# connectors.net
KiCad netlist of a schematic drawn in Altium Designer
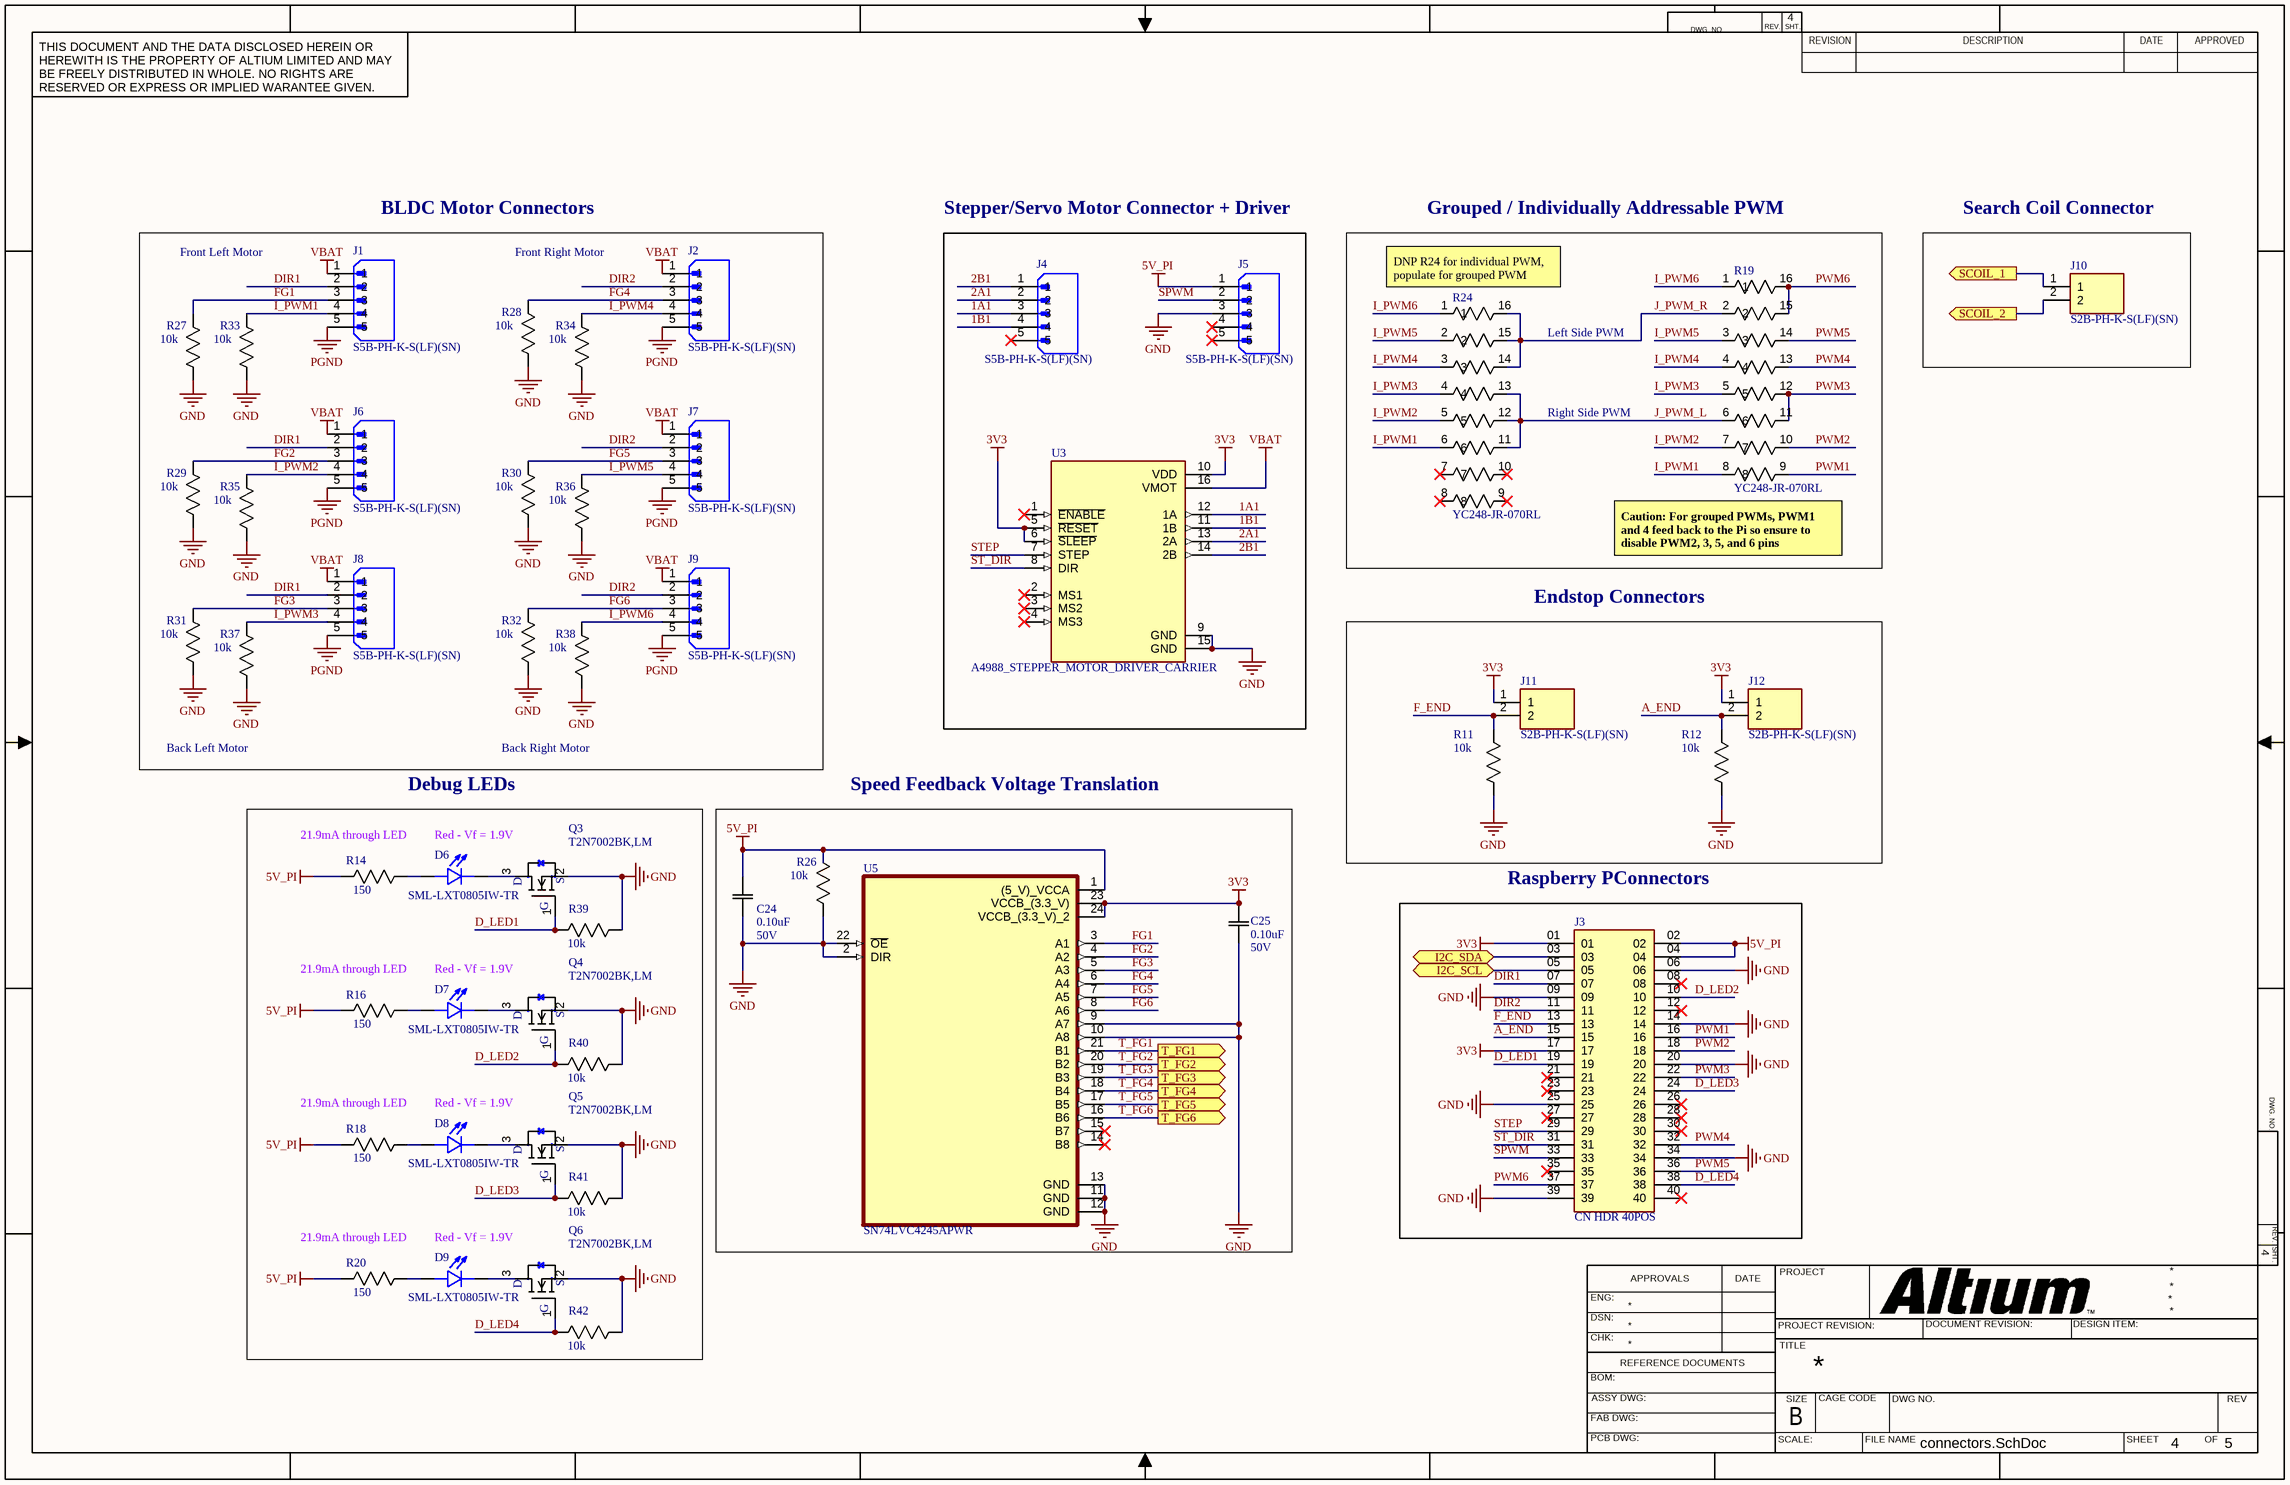
[diagram p0: connectors.SchDoc]

(export (version "E")
  (design (tool "Eeschema 10.0.6"))
  (components
    (comp (ref "C24")
      (value "0.10uF")
      (footprint "0805")
      (description "Default Symbol for Capacitors")
      (fields
        (field (name "RATING") "50V")
        (field (name "PART NUMBER") "CAP 0.1uF 50V")
        (field (name "TOLERANCE") "10%")
      )
      (libsource (lib "capacitor_library") (part "CAP_Default"))
    )
    (comp (ref "C25")
      (value "0.10uF")
      (footprint "0805")
      (description "Default Symbol for Capacitors")
      (fields
        (field (name "RATING") "50V")
        (field (name "PART NUMBER") "CAP 0.1uF 50V")
        (field (name "TOLERANCE") "10%")
      )
      (libsource (lib "capacitor_library") (part "CAP_Default"))
    )
    (comp (ref "D6")
      (value "SML-LXT0805IW-TR")
      (footprint "LEDC2012X120N")
      (fields (field (name "MF") "Lumex Opto/Components"))
      (libsource (lib "SML-LXT0805IW-TR") (part "SML-LXT0805IW-TR"))
    )
    (comp (ref "D7")
      (value "SML-LXT0805IW-TR")
      (footprint "LEDC2012X120N")
      (fields (field (name "MF") "Lumex Opto/Components"))
      (libsource (lib "SML-LXT0805IW-TR") (part "SML-LXT0805IW-TR"))
    )
    (comp (ref "D8")
      (value "SML-LXT0805IW-TR")
      (footprint "LEDC2012X120N")
      (fields (field (name "MF") "Lumex Opto/Components"))
      (libsource (lib "SML-LXT0805IW-TR") (part "SML-LXT0805IW-TR"))
    )
    (comp (ref "D9")
      (value "SML-LXT0805IW-TR")
      (footprint "LEDC2012X120N")
      (fields (field (name "MF") "Lumex Opto/Components"))
      (libsource (lib "SML-LXT0805IW-TR") (part "SML-LXT0805IW-TR"))
    )
    (comp (ref "J1")
      (value "S5B-PH-K-S(LF)(SN)")
      (footprint "JST_S5B-PH-K-S(LF)(SN)")
      (description "Connector Header Through Hole, Right Angle 5 position 0.079 (2.00mm)")
      (fields (field (name "MF") "JST Sales America Inc."))
      (libsource (lib "S5B-PH-K-S_LF__SN_") (part "S5B-PH-K-S(LF)(SN)"))
    )
    (comp (ref "J2")
      (value "S5B-PH-K-S(LF)(SN)")
      (footprint "JST_S5B-PH-K-S(LF)(SN)")
      (description "Connector Header Through Hole, Right Angle 5 position 0.079 (2.00mm)")
      (fields (field (name "MF") "JST Sales America Inc."))
      (libsource (lib "S5B-PH-K-S_LF__SN_") (part "S5B-PH-K-S(LF)(SN)"))
    )
    (comp (ref "J3")
      (value "CN HDR 40POS")
      (footprint "CN HDR 40POS 0.1 TH")
      (description "40 Position Header Connector")
      (libsource (lib "Connector_Library") (part "CN HDR 40POS"))
    )
    (comp (ref "J4")
      (value "S5B-PH-K-S(LF)(SN)")
      (footprint "JST_S5B-PH-K-S(LF)(SN)")
      (description "Connector Header Through Hole, Right Angle 5 position 0.079 (2.00mm)")
      (fields (field (name "MF") "JST Sales America Inc."))
      (libsource (lib "S5B-PH-K-S_LF__SN_") (part "S5B-PH-K-S(LF)(SN)"))
    )
    (comp (ref "J5")
      (value "S5B-PH-K-S(LF)(SN)")
      (footprint "JST_S5B-PH-K-S(LF)(SN)")
      (description "Connector Header Through Hole, Right Angle 5 position 0.079 (2.00mm)")
      (fields (field (name "MF") "JST Sales America Inc."))
      (libsource (lib "S5B-PH-K-S_LF__SN_") (part "S5B-PH-K-S(LF)(SN)"))
    )
    (comp (ref "J6")
      (value "S5B-PH-K-S(LF)(SN)")
      (footprint "JST_S5B-PH-K-S(LF)(SN)")
      (description "Connector Header Through Hole, Right Angle 5 position 0.079 (2.00mm)")
      (fields (field (name "MF") "JST Sales America Inc."))
      (libsource (lib "S5B-PH-K-S_LF__SN_") (part "S5B-PH-K-S(LF)(SN)"))
    )
    (comp (ref "J7")
      (value "S5B-PH-K-S(LF)(SN)")
      (footprint "JST_S5B-PH-K-S(LF)(SN)")
      (description "Connector Header Through Hole, Right Angle 5 position 0.079 (2.00mm)")
      (fields (field (name "MF") "JST Sales America Inc."))
      (libsource (lib "S5B-PH-K-S_LF__SN_") (part "S5B-PH-K-S(LF)(SN)"))
    )
    (comp (ref "J8")
      (value "S5B-PH-K-S(LF)(SN)")
      (footprint "JST_S5B-PH-K-S(LF)(SN)")
      (description "Connector Header Through Hole, Right Angle 5 position 0.079 (2.00mm)")
      (fields (field (name "MF") "JST Sales America Inc."))
      (libsource (lib "S5B-PH-K-S_LF__SN_") (part "S5B-PH-K-S(LF)(SN)"))
    )
    (comp (ref "J9")
      (value "S5B-PH-K-S(LF)(SN)")
      (footprint "JST_S5B-PH-K-S(LF)(SN)")
      (description "Connector Header Through Hole, Right Angle 5 position 0.079 (2.00mm)")
      (fields (field (name "MF") "JST Sales America Inc."))
      (libsource (lib "S5B-PH-K-S_LF__SN_") (part "S5B-PH-K-S(LF)(SN)"))
    )
    (comp (ref "J10")
      (value "S2B-PH-K-S(LF)(SN)")
      (footprint "JST_S2B-PH-K-S(LF)(SN)")
      (description "Connector Header Through Hole, Right Angle 2 position")
      (fields (field (name "MF") "JST Sales America Inc."))
      (libsource (lib "S2B-PH-K-S_LF__SN_") (part "S2B-PH-K-S(LF)(SN)"))
    )
    (comp (ref "J11")
      (value "S2B-PH-K-S(LF)(SN)")
      (footprint "JST_S2B-PH-K-S(LF)(SN)")
      (description "Connector Header Through Hole, Right Angle 2 position")
      (fields (field (name "MF") "JST Sales America Inc."))
      (libsource (lib "S2B-PH-K-S_LF__SN_") (part "S2B-PH-K-S(LF)(SN)"))
    )
    (comp (ref "J12")
      (value "S2B-PH-K-S(LF)(SN)")
      (footprint "JST_S2B-PH-K-S(LF)(SN)")
      (description "Connector Header Through Hole, Right Angle 2 position")
      (fields (field (name "MF") "JST Sales America Inc."))
      (libsource (lib "S2B-PH-K-S_LF__SN_") (part "S2B-PH-K-S(LF)(SN)"))
    )
    (comp (ref "Q3")
      (value "T2N7002BK,LM")
      (footprint "SOT23_TOS")
      (description "No Description Available")
      (libsource (lib "T2N7002BK,LM") (part "T2N7002BK,LM"))
    )
    (comp (ref "Q4")
      (value "T2N7002BK,LM")
      (footprint "SOT23_TOS")
      (description "No Description Available")
      (libsource (lib "T2N7002BK,LM") (part "T2N7002BK,LM"))
    )
    (comp (ref "Q5")
      (value "T2N7002BK,LM")
      (footprint "SOT23_TOS")
      (description "No Description Available")
      (libsource (lib "T2N7002BK,LM") (part "T2N7002BK,LM"))
    )
    (comp (ref "Q6")
      (value "T2N7002BK,LM")
      (footprint "SOT23_TOS")
      (description "No Description Available")
      (libsource (lib "T2N7002BK,LM") (part "T2N7002BK,LM"))
    )
    (comp (ref "R11")
      (value "10k")
      (footprint "0805")
      (description "RES SMD 10K OHM 1% 1/8W 0603")
      (fields (field (name "TOLERANCE") "5%") (field (name "PART NUMBER") "RES 10k 1/8W - 1%"))
      (libsource (lib "Resistor_Library") (part "RES 10k 1/8W 1%"))
    )
    (comp (ref "R12")
      (value "10k")
      (footprint "0805")
      (description "RES SMD 10K OHM 1% 1/8W 0603")
      (fields (field (name "TOLERANCE") "5%") (field (name "PART NUMBER") "RES 10k 1/8W - 1%"))
      (libsource (lib "Resistor_Library") (part "RES 10k 1/8W 1%"))
    )
    (comp (ref "R14")
      (value "150")
      (footprint "0805")
      (description "Default Resistor Symbol")
      (fields (field (name "TOLERANCE") "5%") (field (name "PART NUMBER") "RES 150.0 1/8W"))
      (libsource (lib "") (part "RES_DEFAULT_1"))
    )
    (comp (ref "R16")
      (value "150")
      (footprint "0805")
      (description "Default Resistor Symbol")
      (fields (field (name "TOLERANCE") "5%") (field (name "PART NUMBER") "RES 150.0 1/8W"))
      (libsource (lib "") (part "RES_DEFAULT_1"))
    )
    (comp (ref "R18")
      (value "150")
      (footprint "0805")
      (description "Default Resistor Symbol")
      (fields (field (name "TOLERANCE") "5%") (field (name "PART NUMBER") "RES 150.0 1/8W"))
      (libsource (lib "") (part "RES_DEFAULT_1"))
    )
    (comp (ref "R19")
      (value "YC248-JR-070RL")
      (footprint "RES_YC248_4X1P6_YAG-M")
      (description "No Description Available")
      (libsource (lib "YC248-JR-070RL") (part "YC248-JR-070RL"))
    )
    (comp (ref "R20")
      (value "150")
      (footprint "0805")
      (description "Default Resistor Symbol")
      (fields (field (name "TOLERANCE") "5%") (field (name "PART NUMBER") "RES 150.0 1/8W"))
      (libsource (lib "Resistor_Library") (part "RES_DEFAULT"))
    )
    (comp (ref "R24")
      (value "YC248-JR-070RL")
      (footprint "RES_YC248_4X1P6_YAG-M")
      (description "No Description Available")
      (libsource (lib "YC248-JR-070RL") (part "YC248-JR-070RL"))
    )
    (comp (ref "R26")
      (value "10k")
      (footprint "0805")
      (description "Default Resistor Symbol")
      (fields (field (name "TOLERANCE") "5%") (field (name "PART NUMBER") "RES 10k 1/8W - 1%"))
      (libsource (lib "") (part "RES_DEFAULT_1"))
    )
    (comp (ref "R27")
      (value "10k")
      (footprint "0805")
      (description "Default Resistor Symbol")
      (fields (field (name "TOLERANCE") "5%") (field (name "PART NUMBER") "RES 10k 1/8W - 1%"))
      (libsource (lib "Resistor_Library") (part "RES_DEFAULT"))
    )
    (comp (ref "R28")
      (value "10k")
      (footprint "0805")
      (description "Default Resistor Symbol")
      (fields (field (name "TOLERANCE") "5%") (field (name "PART NUMBER") "RES 10k 1/8W - 1%"))
      (libsource (lib "Resistor_Library") (part "RES_DEFAULT"))
    )
    (comp (ref "R29")
      (value "10k")
      (footprint "0805")
      (description "Default Resistor Symbol")
      (fields (field (name "TOLERANCE") "5%") (field (name "PART NUMBER") "RES 10k 1/8W - 1%"))
      (libsource (lib "Resistor_Library") (part "RES_DEFAULT"))
    )
    (comp (ref "R30")
      (value "10k")
      (footprint "0805")
      (description "Default Resistor Symbol")
      (fields (field (name "TOLERANCE") "5%") (field (name "PART NUMBER") "RES 10k 1/8W - 1%"))
      (libsource (lib "") (part "RES_DEFAULT_1"))
    )
    (comp (ref "R31")
      (value "10k")
      (footprint "0805")
      (description "Default Resistor Symbol")
      (fields (field (name "TOLERANCE") "5%") (field (name "PART NUMBER") "RES 10k 1/8W - 1%"))
      (libsource (lib "") (part "RES_DEFAULT_1"))
    )
    (comp (ref "R32")
      (value "10k")
      (footprint "0805")
      (description "Default Resistor Symbol")
      (fields (field (name "TOLERANCE") "5%") (field (name "PART NUMBER") "RES 10k 1/8W - 1%"))
      (libsource (lib "") (part "RES_DEFAULT_1"))
    )
    (comp (ref "R33")
      (value "10k")
      (footprint "0805")
      (description "Default Resistor Symbol")
      (fields (field (name "TOLERANCE") "5%") (field (name "PART NUMBER") "RES 10k 1/8W - 1%"))
      (libsource (lib "") (part "RES_DEFAULT_1"))
    )
    (comp (ref "R34")
      (value "10k")
      (footprint "0805")
      (description "Default Resistor Symbol")
      (fields (field (name "TOLERANCE") "5%") (field (name "PART NUMBER") "RES 10k 1/8W - 1%"))
      (libsource (lib "Resistor_Library") (part "RES_DEFAULT"))
    )
    (comp (ref "R35")
      (value "10k")
      (footprint "0805")
      (description "Default Resistor Symbol")
      (fields (field (name "TOLERANCE") "5%") (field (name "PART NUMBER") "RES 10k 1/8W - 1%"))
      (libsource (lib "Resistor_Library") (part "RES_DEFAULT"))
    )
    (comp (ref "R36")
      (value "10k")
      (footprint "0805")
      (description "Default Resistor Symbol")
      (fields (field (name "TOLERANCE") "5%") (field (name "PART NUMBER") "RES 10k 1/8W - 1%"))
      (libsource (lib "Resistor_Library") (part "RES_DEFAULT"))
    )
    (comp (ref "R37")
      (value "10k")
      (footprint "0805")
      (description "Default Resistor Symbol")
      (fields (field (name "TOLERANCE") "5%") (field (name "PART NUMBER") "RES 10k 1/8W - 1%"))
      (libsource (lib "Resistor_Library") (part "RES_DEFAULT"))
    )
    (comp (ref "R38")
      (value "10k")
      (footprint "0805")
      (description "Default Resistor Symbol")
      (fields (field (name "TOLERANCE") "5%") (field (name "PART NUMBER") "RES 10k 1/8W - 1%"))
      (libsource (lib "Resistor_Library") (part "RES_DEFAULT"))
    )
    (comp (ref "R39")
      (value "10k")
      (footprint "0805")
      (description "Default Resistor Symbol")
      (fields (field (name "TOLERANCE") "5%") (field (name "PART NUMBER") "RES 10k 1/8W - 1%"))
      (libsource (lib "Resistor_Library") (part "RES_DEFAULT"))
    )
    (comp (ref "R40")
      (value "10k")
      (footprint "0805")
      (description "Default Resistor Symbol")
      (fields (field (name "TOLERANCE") "5%") (field (name "PART NUMBER") "RES 10k 1/8W - 1%"))
      (libsource (lib "Resistor_Library") (part "RES_DEFAULT"))
    )
    (comp (ref "R41")
      (value "10k")
      (footprint "0805")
      (description "Default Resistor Symbol")
      (fields (field (name "TOLERANCE") "5%") (field (name "PART NUMBER") "RES 10k 1/8W - 1%"))
      (libsource (lib "Resistor_Library") (part "RES_DEFAULT"))
    )
    (comp (ref "R42")
      (value "10k")
      (footprint "0805")
      (description "Default Resistor Symbol")
      (fields (field (name "TOLERANCE") "5%") (field (name "PART NUMBER") "RES 10k 1/8W - 1%"))
      (libsource (lib "Resistor_Library") (part "RES_DEFAULT"))
    )
    (comp (ref "U3")
      (value "A4988_STEPPER_MOTOR_DRIVER_CARRIER")
      (footprint "MODULE_A4988_STEPPER_MOTOR_DRIVER_CARRIER")
      (description "Stepper motor controler; IC: A4988; 1A; Uin mot: 8Ã·35V")
      (libsource (lib "A4988_STEPPER_MOTOR_DRIVER_CARRIER") (part "A4988_STEPPER_MOTOR_DRIVER_CARRIER"))
    )
    (comp (ref "U5")
      (value "SN74LVC4245APWR")
      (footprint "SOP65P640X120-24N")
      (description "24-TSSOP -40 ~ 85")
      (fields
        (field (name "MF") "Texas Instruments")
        (field (name "BUYPART") "https://www.snapeda.com/parts/SN74LVC4245APWR/Texas%20Instruments/view-part/235354/?ref=eda")
      )
      (libsource (lib "SN74LVC4245APWR") (part "SN74LVC4245APWR"))
    )
  )
  (nets
    (net (code "1") (name "/1A1") (class "Default")
      (node (ref "J4") (pin "3") (pinfunction "3_3") (pintype "passive"))
      (node (ref "U3") (pin "12") (pinfunction "1A_12") (pintype "output"))
    )
    (net (code "2") (name "/1B1") (class "Default")
      (node (ref "J4") (pin "4") (pinfunction "4_4") (pintype "passive"))
      (node (ref "U3") (pin "11") (pinfunction "1B_11") (pintype "output"))
    )
    (net (code "3") (name "/2A1") (class "Default")
      (node (ref "J4") (pin "2") (pinfunction "2_2") (pintype "passive"))
      (node (ref "U3") (pin "13") (pinfunction "2A_13") (pintype "output"))
    )
    (net (code "4") (name "/2B1") (class "Default")
      (node (ref "J4") (pin "1") (pinfunction "1_1") (pintype "passive"))
      (node (ref "U3") (pin "14") (pinfunction "2B_14") (pintype "output"))
    )
    (net (code "5") (name "/A_END") (class "Default")
      (node (ref "J12") (pin "2") (pinfunction "2_2") (pintype "passive"))
      (node (ref "J3") (pin "15") (pinfunction "15_15") (pintype "passive"))
      (node (ref "R12") (pin "2") (pinfunction "R2_2") (pintype "passive"))
    )
    (net (code "6") (name "/DIR1") (class "Default")
      (node (ref "J1") (pin "2") (pinfunction "2_2") (pintype "passive"))
      (node (ref "J3") (pin "07") (pinfunction "07_07") (pintype "passive"))
      (node (ref "J6") (pin "2") (pinfunction "2_2") (pintype "passive"))
      (node (ref "J8") (pin "2") (pinfunction "2_2") (pintype "passive"))
    )
    (net (code "7") (name "/DIR2") (class "Default")
      (node (ref "J2") (pin "2") (pinfunction "2_2") (pintype "passive"))
      (node (ref "J3") (pin "11") (pinfunction "11_11") (pintype "passive"))
      (node (ref "J7") (pin "2") (pinfunction "2_2") (pintype "passive"))
      (node (ref "J9") (pin "2") (pinfunction "2_2") (pintype "passive"))
    )
    (net (code "8") (name "/D_LED1") (class "Default")
      (node (ref "J3") (pin "19") (pinfunction "19_19") (pintype "passive"))
      (node (ref "Q3") (pin "1") (pinfunction "G_1") (pintype "passive"))
      (node (ref "R39") (pin "2") (pinfunction "R2_2") (pintype "passive"))
    )
    (net (code "9") (name "/D_LED2") (class "Default")
      (node (ref "J3") (pin "10") (pinfunction "10_10") (pintype "passive"))
      (node (ref "Q4") (pin "1") (pinfunction "G_1") (pintype "passive"))
      (node (ref "R40") (pin "2") (pinfunction "R2_2") (pintype "passive"))
    )
    (net (code "10") (name "/D_LED3") (class "Default")
      (node (ref "J3") (pin "24") (pinfunction "24_24") (pintype "passive"))
      (node (ref "Q5") (pin "1") (pinfunction "G_1") (pintype "passive"))
      (node (ref "R41") (pin "2") (pinfunction "R2_2") (pintype "passive"))
    )
    (net (code "11") (name "/D_LED4") (class "Default")
      (node (ref "J3") (pin "38") (pinfunction "38_38") (pintype "passive"))
      (node (ref "Q6") (pin "1") (pinfunction "G_1") (pintype "passive"))
      (node (ref "R42") (pin "2") (pinfunction "R2_2") (pintype "passive"))
    )
    (net (code "12") (name "/FG1") (class "Default")
      (node (ref "J1") (pin "3") (pinfunction "3_3") (pintype "passive"))
      (node (ref "R27") (pin "1") (pinfunction "R1_1") (pintype "passive"))
      (node (ref "U5") (pin "3") (pinfunction "A1_3") (pintype "output"))
    )
    (net (code "13") (name "/FG2") (class "Default")
      (node (ref "J6") (pin "3") (pinfunction "3_3") (pintype "passive"))
      (node (ref "R29") (pin "1") (pinfunction "R1_1") (pintype "passive"))
      (node (ref "U5") (pin "4") (pinfunction "A2_4") (pintype "output"))
    )
    (net (code "14") (name "/FG3") (class "Default")
      (node (ref "J8") (pin "3") (pinfunction "3_3") (pintype "passive"))
      (node (ref "R31") (pin "1") (pinfunction "R1_1") (pintype "passive"))
      (node (ref "U5") (pin "5") (pinfunction "A3_5") (pintype "output"))
    )
    (net (code "15") (name "/FG4") (class "Default")
      (node (ref "J2") (pin "3") (pinfunction "3_3") (pintype "passive"))
      (node (ref "R28") (pin "1") (pinfunction "R1_1") (pintype "passive"))
      (node (ref "U5") (pin "6") (pinfunction "A4_6") (pintype "output"))
    )
    (net (code "16") (name "/FG5") (class "Default")
      (node (ref "J7") (pin "3") (pinfunction "3_3") (pintype "passive"))
      (node (ref "R30") (pin "1") (pinfunction "R1_1") (pintype "passive"))
      (node (ref "U5") (pin "7") (pinfunction "A5_7") (pintype "output"))
    )
    (net (code "17") (name "/FG6") (class "Default")
      (node (ref "J9") (pin "3") (pinfunction "3_3") (pintype "passive"))
      (node (ref "R32") (pin "1") (pinfunction "R1_1") (pintype "passive"))
      (node (ref "U5") (pin "8") (pinfunction "A6_8") (pintype "output"))
    )
    (net (code "18") (name "/F_END") (class "Default")
      (node (ref "J11") (pin "2") (pinfunction "2_2") (pintype "passive"))
      (node (ref "J3") (pin "13") (pinfunction "13_13") (pintype "passive"))
      (node (ref "R11") (pin "2") (pinfunction "R2_2") (pintype "passive"))
    )
    (net (code "19") (name "/I2C_SCL") (class "Default")
      (node (ref "J3") (pin "05") (pinfunction "05_05") (pintype "passive"))
    )
    (net (code "20") (name "/I2C_SDA") (class "Default")
      (node (ref "J3") (pin "03") (pinfunction "03_03") (pintype "passive"))
    )
    (net (code "21") (name "/I_PWM1") (class "Default")
      (node (ref "J1") (pin "4") (pinfunction "4_4") (pintype "passive"))
      (node (ref "R19") (pin "8") (pinfunction "8_8") (pintype "passive"))
      (node (ref "R24") (pin "6") (pinfunction "6_6") (pintype "passive"))
      (node (ref "R33") (pin "1") (pinfunction "R1_1") (pintype "passive"))
    )
    (net (code "22") (name "/I_PWM2") (class "Default")
      (node (ref "J6") (pin "4") (pinfunction "4_4") (pintype "passive"))
      (node (ref "R19") (pin "7") (pinfunction "7_7") (pintype "passive"))
      (node (ref "R24") (pin "5") (pinfunction "5_5") (pintype "passive"))
      (node (ref "R35") (pin "1") (pinfunction "R1_1") (pintype "passive"))
    )
    (net (code "23") (name "/I_PWM3") (class "Default")
      (node (ref "J8") (pin "4") (pinfunction "4_4") (pintype "passive"))
      (node (ref "R19") (pin "5") (pinfunction "5_5") (pintype "passive"))
      (node (ref "R24") (pin "4") (pinfunction "4_4") (pintype "passive"))
      (node (ref "R37") (pin "1") (pinfunction "R1_1") (pintype "passive"))
    )
    (net (code "24") (name "/I_PWM4") (class "Default")
      (node (ref "J2") (pin "4") (pinfunction "4_4") (pintype "passive"))
      (node (ref "R19") (pin "4") (pinfunction "4_4") (pintype "passive"))
      (node (ref "R24") (pin "3") (pinfunction "3_3") (pintype "passive"))
      (node (ref "R34") (pin "1") (pinfunction "R1_1") (pintype "passive"))
    )
    (net (code "25") (name "/I_PWM5") (class "Default")
      (node (ref "J7") (pin "4") (pinfunction "4_4") (pintype "passive"))
      (node (ref "R19") (pin "3") (pinfunction "3_3") (pintype "passive"))
      (node (ref "R24") (pin "2") (pinfunction "2_2") (pintype "passive"))
      (node (ref "R36") (pin "1") (pinfunction "R1_1") (pintype "passive"))
    )
    (net (code "26") (name "/I_PWM6") (class "Default")
      (node (ref "J9") (pin "4") (pinfunction "4_4") (pintype "passive"))
      (node (ref "R19") (pin "1") (pinfunction "1_1") (pintype "passive"))
      (node (ref "R24") (pin "1") (pinfunction "1_1") (pintype "passive"))
      (node (ref "R38") (pin "1") (pinfunction "R1_1") (pintype "passive"))
    )
    (net (code "27") (name "/J_PWM_L") (class "Default")
      (node (ref "R19") (pin "6") (pinfunction "6_6") (pintype "passive"))
      (node (ref "R24") (pin "11") (pinfunction "11_11") (pintype "passive"))
      (node (ref "R24") (pin "12") (pinfunction "12_12") (pintype "passive"))
      (node (ref "R24") (pin "13") (pinfunction "13_13") (pintype "passive"))
    )
    (net (code "28") (name "/J_PWM_R") (class "Default")
      (node (ref "R19") (pin "2") (pinfunction "2_2") (pintype "passive"))
      (node (ref "R24") (pin "14") (pinfunction "14_14") (pintype "passive"))
      (node (ref "R24") (pin "15") (pinfunction "15_15") (pintype "passive"))
      (node (ref "R24") (pin "16") (pinfunction "16_16") (pintype "passive"))
    )
    (net (code "29") (name "/PWM1") (class "Default")
      (node (ref "J3") (pin "16") (pinfunction "16_16") (pintype "passive"))
      (node (ref "R19") (pin "9") (pinfunction "9_9") (pintype "passive"))
    )
    (net (code "30") (name "/PWM2") (class "Default")
      (node (ref "J3") (pin "18") (pinfunction "18_18") (pintype "passive"))
      (node (ref "R19") (pin "10") (pinfunction "10_10") (pintype "passive"))
    )
    (net (code "31") (name "/PWM3") (class "Default")
      (node (ref "J3") (pin "22") (pinfunction "22_22") (pintype "passive"))
      (node (ref "R19") (pin "11") (pinfunction "11_11") (pintype "passive"))
      (node (ref "R19") (pin "12") (pinfunction "12_12") (pintype "passive"))
    )
    (net (code "32") (name "/PWM4") (class "Default")
      (node (ref "J3") (pin "32") (pinfunction "32_32") (pintype "passive"))
      (node (ref "R19") (pin "13") (pinfunction "13_13") (pintype "passive"))
    )
    (net (code "33") (name "/PWM5") (class "Default")
      (node (ref "J3") (pin "36") (pinfunction "36_36") (pintype "passive"))
      (node (ref "R19") (pin "14") (pinfunction "14_14") (pintype "passive"))
    )
    (net (code "34") (name "/PWM6") (class "Default")
      (node (ref "J3") (pin "37") (pinfunction "37_37") (pintype "passive"))
      (node (ref "R19") (pin "15") (pinfunction "15_15") (pintype "passive"))
      (node (ref "R19") (pin "16") (pinfunction "16_16") (pintype "passive"))
    )
    (net (code "35") (name "/SCOIL_1") (class "Default")
      (node (ref "J10") (pin "1") (pinfunction "1_1") (pintype "passive"))
    )
    (net (code "36") (name "/SCOIL_2") (class "Default")
      (node (ref "J10") (pin "2") (pinfunction "2_2") (pintype "passive"))
    )
    (net (code "37") (name "/SPWM") (class "Default")
      (node (ref "J3") (pin "33") (pinfunction "33_33") (pintype "passive"))
      (node (ref "J5") (pin "2") (pinfunction "2_2") (pintype "passive"))
    )
    (net (code "38") (name "/STEP") (class "Default")
      (node (ref "J3") (pin "29") (pinfunction "29_29") (pintype "passive"))
      (node (ref "U3") (pin "7") (pinfunction "STEP_7") (pintype "input"))
    )
    (net (code "39") (name "/ST_DIR") (class "Default")
      (node (ref "J3") (pin "31") (pinfunction "31_31") (pintype "passive"))
      (node (ref "U3") (pin "8") (pinfunction "DIR_8") (pintype "input"))
    )
    (net (code "40") (name "/T_FG1") (class "Default")
      (node (ref "U5") (pin "21") (pinfunction "B1_21") (pintype "output"))
    )
    (net (code "41") (name "/T_FG2") (class "Default")
      (node (ref "U5") (pin "20") (pinfunction "B2_20") (pintype "output"))
    )
    (net (code "42") (name "/T_FG3") (class "Default")
      (node (ref "U5") (pin "19") (pinfunction "B3_19") (pintype "output"))
    )
    (net (code "43") (name "/T_FG4") (class "Default")
      (node (ref "U5") (pin "18") (pinfunction "B4_18") (pintype "output"))
    )
    (net (code "44") (name "/T_FG5") (class "Default")
      (node (ref "U5") (pin "17") (pinfunction "B5_17") (pintype "output"))
    )
    (net (code "45") (name "/T_FG6") (class "Default")
      (node (ref "U5") (pin "16") (pinfunction "B6_16") (pintype "output"))
    )
    (net (code "46") (name "3V3") (class "Default")
      (node (ref "C25") (pin "2") (pinfunction "C2_2") (pintype "passive"))
      (node (ref "J11") (pin "1") (pinfunction "1_1") (pintype "passive"))
      (node (ref "J12") (pin "1") (pinfunction "1_1") (pintype "passive"))
      (node (ref "J3") (pin "01") (pinfunction "01_01") (pintype "passive"))
      (node (ref "J3") (pin "17") (pinfunction "17_17") (pintype "passive"))
      (node (ref "U3") (pin "10") (pinfunction "VDD_10") (pintype "power_in"))
      (node (ref "U3") (pin "5") (pinfunction "~{RESET}_5") (pintype "input"))
      (node (ref "U3") (pin "6") (pinfunction "~{SLEEP}_6") (pintype "input"))
      (node (ref "U5") (pin "23") (pinfunction "VCCB_(3.3_V)_23") (pintype "power_in"))
      (node (ref "U5") (pin "24") (pinfunction "VCCB_(3.3_V)_2_24") (pintype "power_in"))
    )
    (net (code "47") (name "5V_PI") (class "Default")
      (node (ref "C24") (pin "2") (pinfunction "C2_2") (pintype "passive"))
      (node (ref "J3") (pin "02") (pinfunction "02_02") (pintype "passive"))
      (node (ref "J3") (pin "04") (pinfunction "04_04") (pintype "passive"))
      (node (ref "J5") (pin "1") (pinfunction "1_1") (pintype "passive"))
      (node (ref "R14") (pin "2") (pinfunction "R2_2") (pintype "passive"))
      (node (ref "R16") (pin "2") (pinfunction "R2_2") (pintype "passive"))
      (node (ref "R18") (pin "2") (pinfunction "R2_2") (pintype "passive"))
      (node (ref "R20") (pin "2") (pinfunction "R2_2") (pintype "passive"))
      (node (ref "R26") (pin "1") (pinfunction "R1_1") (pintype "passive"))
      (node (ref "U5") (pin "1") (pinfunction "(5_V)_VCCA_1") (pintype "power_in"))
    )
    (net (code "48") (name "GND") (class "Default")
      (node (ref "C24") (pin "1") (pinfunction "C1_1") (pintype "passive"))
      (node (ref "C25") (pin "1") (pinfunction "C1_1") (pintype "passive"))
      (node (ref "J3") (pin "06") (pinfunction "06_06") (pintype "passive"))
      (node (ref "J3") (pin "09") (pinfunction "09_09") (pintype "passive"))
      (node (ref "J3") (pin "14") (pinfunction "14_14") (pintype "passive"))
      (node (ref "J3") (pin "20") (pinfunction "20_20") (pintype "passive"))
      (node (ref "J3") (pin "25") (pinfunction "25_25") (pintype "passive"))
      (node (ref "J3") (pin "34") (pinfunction "34_34") (pintype "passive"))
      (node (ref "J3") (pin "39") (pinfunction "39_39") (pintype "passive"))
      (node (ref "J5") (pin "3") (pinfunction "3_3") (pintype "passive"))
      (node (ref "Q3") (pin "2") (pinfunction "S_2") (pintype "passive"))
      (node (ref "Q4") (pin "2") (pinfunction "S_2") (pintype "passive"))
      (node (ref "Q5") (pin "2") (pinfunction "S_2") (pintype "passive"))
      (node (ref "Q6") (pin "2") (pinfunction "S_2") (pintype "passive"))
      (node (ref "R11") (pin "1") (pinfunction "R1_1") (pintype "passive"))
      (node (ref "R12") (pin "1") (pinfunction "R1_1") (pintype "passive"))
      (node (ref "R26") (pin "2") (pinfunction "R2_2") (pintype "passive"))
      (node (ref "R27") (pin "2") (pinfunction "R2_2") (pintype "passive"))
      (node (ref "R28") (pin "2") (pinfunction "R2_2") (pintype "passive"))
      (node (ref "R29") (pin "2") (pinfunction "R2_2") (pintype "passive"))
      (node (ref "R30") (pin "2") (pinfunction "R2_2") (pintype "passive"))
      (node (ref "R31") (pin "2") (pinfunction "R2_2") (pintype "passive"))
      (node (ref "R32") (pin "2") (pinfunction "R2_2") (pintype "passive"))
      (node (ref "R33") (pin "2") (pinfunction "R2_2") (pintype "passive"))
      (node (ref "R34") (pin "2") (pinfunction "R2_2") (pintype "passive"))
      (node (ref "R35") (pin "2") (pinfunction "R2_2") (pintype "passive"))
      (node (ref "R36") (pin "2") (pinfunction "R2_2") (pintype "passive"))
      (node (ref "R37") (pin "2") (pinfunction "R2_2") (pintype "passive"))
      (node (ref "R38") (pin "2") (pinfunction "R2_2") (pintype "passive"))
      (node (ref "R39") (pin "1") (pinfunction "R1_1") (pintype "passive"))
      (node (ref "R40") (pin "1") (pinfunction "R1_1") (pintype "passive"))
      (node (ref "R41") (pin "1") (pinfunction "R1_1") (pintype "passive"))
      (node (ref "R42") (pin "1") (pinfunction "R1_1") (pintype "passive"))
      (node (ref "U3") (pin "15") (pinfunction "GND_15") (pintype "power_in"))
      (node (ref "U3") (pin "9") (pinfunction "GND_9") (pintype "power_in"))
      (node (ref "U5") (pin "10") (pinfunction "A8_10") (pintype "output"))
      (node (ref "U5") (pin "11") (pinfunction "GND_11") (pintype "power_in"))
      (node (ref "U5") (pin "12") (pinfunction "GND_12") (pintype "power_in"))
      (node (ref "U5") (pin "13") (pinfunction "GND_13") (pintype "power_in"))
      (node (ref "U5") (pin "2") (pinfunction "DIR_2") (pintype "input"))
      (node (ref "U5") (pin "22") (pinfunction "~{OE}_22") (pintype "input"))
      (node (ref "U5") (pin "9") (pinfunction "A7_9") (pintype "output"))
    )
    (net (code "49") (name "Net-(Q3-D)") (class "Default")
      (node (ref "D6") (pin "C") (pinfunction "C_C") (pintype "passive"))
      (node (ref "Q3") (pin "3") (pinfunction "D_3") (pintype "passive"))
    )
    (net (code "50") (name "Net-(Q4-D)") (class "Default")
      (node (ref "D7") (pin "C") (pinfunction "C_C") (pintype "passive"))
      (node (ref "Q4") (pin "3") (pinfunction "D_3") (pintype "passive"))
    )
    (net (code "51") (name "Net-(Q5-D)") (class "Default")
      (node (ref "D8") (pin "C") (pinfunction "C_C") (pintype "passive"))
      (node (ref "Q5") (pin "3") (pinfunction "D_3") (pintype "passive"))
    )
    (net (code "52") (name "Net-(Q6-D)") (class "Default")
      (node (ref "D9") (pin "C") (pinfunction "C_C") (pintype "passive"))
      (node (ref "Q6") (pin "3") (pinfunction "D_3") (pintype "passive"))
    )
    (net (code "53") (name "Net-(R14-R1)") (class "Default")
      (node (ref "D6") (pin "A") (pinfunction "A_A") (pintype "passive"))
      (node (ref "R14") (pin "1") (pinfunction "R1_1") (pintype "passive"))
    )
    (net (code "54") (name "Net-(R16-R1)") (class "Default")
      (node (ref "D7") (pin "A") (pinfunction "A_A") (pintype "passive"))
      (node (ref "R16") (pin "1") (pinfunction "R1_1") (pintype "passive"))
    )
    (net (code "55") (name "Net-(R18-R1)") (class "Default")
      (node (ref "D8") (pin "A") (pinfunction "A_A") (pintype "passive"))
      (node (ref "R18") (pin "1") (pinfunction "R1_1") (pintype "passive"))
    )
    (net (code "56") (name "Net-(R20-R1)") (class "Default")
      (node (ref "D9") (pin "A") (pinfunction "A_A") (pintype "passive"))
      (node (ref "R20") (pin "1") (pinfunction "R1_1") (pintype "passive"))
    )
    (net (code "57") (name "PGND") (class "Default")
      (node (ref "J1") (pin "5") (pinfunction "5_5") (pintype "passive"))
      (node (ref "J2") (pin "5") (pinfunction "5_5") (pintype "passive"))
      (node (ref "J6") (pin "5") (pinfunction "5_5") (pintype "passive"))
      (node (ref "J7") (pin "5") (pinfunction "5_5") (pintype "passive"))
      (node (ref "J8") (pin "5") (pinfunction "5_5") (pintype "passive"))
      (node (ref "J9") (pin "5") (pinfunction "5_5") (pintype "passive"))
    )
    (net (code "58") (name "VBAT") (class "Default")
      (node (ref "J1") (pin "1") (pinfunction "1_1") (pintype "passive"))
      (node (ref "J2") (pin "1") (pinfunction "1_1") (pintype "passive"))
      (node (ref "J6") (pin "1") (pinfunction "1_1") (pintype "passive"))
      (node (ref "J7") (pin "1") (pinfunction "1_1") (pintype "passive"))
      (node (ref "J8") (pin "1") (pinfunction "1_1") (pintype "passive"))
      (node (ref "J9") (pin "1") (pinfunction "1_1") (pintype "passive"))
      (node (ref "U3") (pin "16") (pinfunction "VMOT_16") (pintype "power_in"))
    )
    (net (code "59") (name "unconnected-(J3-Pad08)") (class "Default")
      (node (ref "J3") (pin "08") (pinfunction "08_08") (pintype "passive+no_connect"))
    )
    (net (code "60") (name "unconnected-(J3-Pad12)") (class "Default")
      (node (ref "J3") (pin "12") (pinfunction "12_12") (pintype "passive+no_connect"))
    )
    (net (code "61") (name "unconnected-(J3-Pad21)") (class "Default")
      (node (ref "J3") (pin "21") (pinfunction "21_21") (pintype "passive+no_connect"))
    )
    (net (code "62") (name "unconnected-(J3-Pad23)") (class "Default")
      (node (ref "J3") (pin "23") (pinfunction "23_23") (pintype "passive+no_connect"))
    )
    (net (code "63") (name "unconnected-(J3-Pad26)") (class "Default")
      (node (ref "J3") (pin "26") (pinfunction "26_26") (pintype "passive+no_connect"))
    )
    (net (code "64") (name "unconnected-(J3-Pad27)") (class "Default")
      (node (ref "J3") (pin "27") (pinfunction "27_27") (pintype "passive+no_connect"))
    )
    (net (code "65") (name "unconnected-(J3-Pad28)") (class "Default")
      (node (ref "J3") (pin "28") (pinfunction "28_28") (pintype "passive+no_connect"))
    )
    (net (code "66") (name "unconnected-(J3-Pad30)") (class "Default")
      (node (ref "J3") (pin "30") (pinfunction "30_30") (pintype "passive+no_connect"))
    )
    (net (code "67") (name "unconnected-(J3-Pad35)") (class "Default")
      (node (ref "J3") (pin "35") (pinfunction "35_35") (pintype "passive+no_connect"))
    )
    (net (code "68") (name "unconnected-(J3-Pad40)") (class "Default")
      (node (ref "J3") (pin "40") (pinfunction "40_40") (pintype "passive+no_connect"))
    )
    (net (code "69") (name "unconnected-(J4-Pad5)") (class "Default")
      (node (ref "J4") (pin "5") (pinfunction "5_5") (pintype "passive+no_connect"))
    )
    (net (code "70") (name "unconnected-(J5-Pad4)") (class "Default")
      (node (ref "J5") (pin "4") (pinfunction "4_4") (pintype "passive+no_connect"))
    )
    (net (code "71") (name "unconnected-(J5-Pad5)") (class "Default")
      (node (ref "J5") (pin "5") (pinfunction "5_5") (pintype "passive+no_connect"))
    )
    (net (code "72") (name "unconnected-(R24-Pad7)") (class "Default")
      (node (ref "R24") (pin "7") (pinfunction "7_7") (pintype "passive+no_connect"))
    )
    (net (code "73") (name "unconnected-(R24-Pad8)") (class "Default")
      (node (ref "R24") (pin "8") (pinfunction "8_8") (pintype "passive+no_connect"))
    )
    (net (code "74") (name "unconnected-(R24-Pad9)") (class "Default")
      (node (ref "R24") (pin "9") (pinfunction "9_9") (pintype "passive+no_connect"))
    )
    (net (code "75") (name "unconnected-(R24-Pad10)") (class "Default")
      (node (ref "R24") (pin "10") (pinfunction "10_10") (pintype "passive+no_connect"))
    )
    (net (code "76") (name "unconnected-(U3-MS1-Pad2)") (class "Default")
      (node (ref "U3") (pin "2") (pinfunction "MS1_2") (pintype "input+no_connect"))
    )
    (net (code "77") (name "unconnected-(U3-MS2-Pad3)") (class "Default")
      (node (ref "U3") (pin "3") (pinfunction "MS2_3") (pintype "input+no_connect"))
    )
    (net (code "78") (name "unconnected-(U3-MS3-Pad4)") (class "Default")
      (node (ref "U3") (pin "4") (pinfunction "MS3_4") (pintype "input+no_connect"))
    )
    (net (code "79") (name "unconnected-(U3-~{ENABLE}-Pad1)") (class "Default")
      (node (ref "U3") (pin "1") (pinfunction "~{ENABLE}_1") (pintype "input+no_connect"))
    )
    (net (code "80") (name "unconnected-(U5-B7-Pad15)") (class "Default")
      (node (ref "U5") (pin "15") (pinfunction "B7_15") (pintype "output+no_connect"))
    )
    (net (code "81") (name "unconnected-(U5-B8-Pad14)") (class "Default")
      (node (ref "U5") (pin "14") (pinfunction "B8_14") (pintype "output+no_connect"))
    )
  )
)
